# untitled.net
KiCad netlist of a schematic drawn in EAGLE
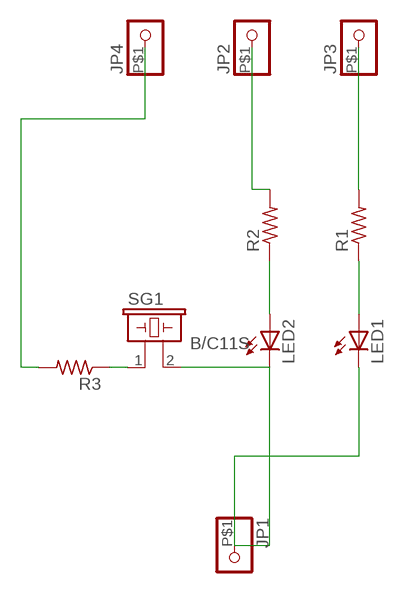
[diagram p0: schematic, sheet 1]

(export (version "E")
  (design (tool "Eeschema 10.0.6"))
  (components
    (comp (ref "JP1")
      (value "PINHD-1X1-BIGPOGO")
      (footprint "eagle-import:1X1-BIGPOGO")
      (libsource (lib "eagle-import") (part "PINHD-1X1-BIGPOGO"))
    )
    (comp (ref "JP2")
      (value "PINHD-1X1-BIGPOGO")
      (footprint "eagle-import:1X1-BIGPOGO")
      (libsource (lib "eagle-import") (part "PINHD-1X1-BIGPOGO"))
    )
    (comp (ref "JP3")
      (value "PINHD-1X1-BIGPOGO")
      (footprint "eagle-import:1X1-BIGPOGO")
      (libsource (lib "eagle-import") (part "PINHD-1X1-BIGPOGO"))
    )
    (comp (ref "JP4")
      (value "PINHD-1X1-BIGPOGO")
      (footprint "eagle-import:1X1-BIGPOGO")
      (libsource (lib "eagle-import") (part "PINHD-1X1-BIGPOGO"))
    )
    (comp (ref "LED1")
      (value "LEDB152")
      (footprint "eagle-import:Q62902-B152")
      (libsource (lib "eagle-import") (part "LEDB152"))
    )
    (comp (ref "LED2")
      (value "LEDB152")
      (footprint "eagle-import:Q62902-B152")
      (libsource (lib "eagle-import") (part "LEDB152"))
    )
    (comp (ref "R1")
      (value "FLIPFLOP-RES")
      (footprint "eagle-import:0805-THM")
      (libsource (lib "eagle-import") (part "FLIPFLOP-RES"))
    )
    (comp (ref "R2")
      (value "FLIPFLOP-RES")
      (footprint "eagle-import:0805-THM")
      (libsource (lib "eagle-import") (part "FLIPFLOP-RES"))
    )
    (comp (ref "R3")
      (value "FLIPFLOP-RES")
      (footprint "eagle-import:0805-THM")
      (libsource (lib "eagle-import") (part "FLIPFLOP-RES"))
    )
    (comp (ref "SG1")
      (value "B/C11S")
      (footprint "eagle-import:B_C11S")
      (libsource (lib "eagle-import") (part "B/C11S"))
    )
  )
  (nets
    (net (code "1") (name "Net-(JP1-1)") (class "Default")
      (node (ref "JP1") (pin "P$1") (pinfunction "1_P$1") (pintype "passive"))
      (node (ref "LED1") (pin "K") (pinfunction "C_K") (pintype "passive"))
      (node (ref "LED2") (pin "K") (pinfunction "C_K") (pintype "passive"))
      (node (ref "SG1") (pin "2") (pinfunction "2_2") (pintype "passive"))
    )
    (net (code "2") (name "Net-(JP2-1)") (class "Default")
      (node (ref "JP2") (pin "P$1") (pinfunction "1_P$1") (pintype "passive"))
      (node (ref "R2") (pin "2") (pinfunction "2_2") (pintype "passive"))
    )
    (net (code "3") (name "Net-(JP3-1)") (class "Default")
      (node (ref "JP3") (pin "P$1") (pinfunction "1_P$1") (pintype "passive"))
      (node (ref "R1") (pin "2") (pinfunction "2_2") (pintype "passive"))
    )
    (net (code "4") (name "Net-(JP4-1)") (class "Default")
      (node (ref "JP4") (pin "P$1") (pinfunction "1_P$1") (pintype "passive"))
      (node (ref "R3") (pin "2") (pinfunction "2_2") (pintype "passive"))
    )
    (net (code "5") (name "Net-(LED1-PadA)") (class "Default")
      (node (ref "LED1") (pin "A") (pinfunction "A_A") (pintype "passive"))
      (node (ref "R1") (pin "1") (pinfunction "1_1") (pintype "passive"))
    )
    (net (code "6") (name "Net-(LED2-PadA)") (class "Default")
      (node (ref "LED2") (pin "A") (pinfunction "A_A") (pintype "passive"))
      (node (ref "R2") (pin "1") (pinfunction "1_1") (pintype "passive"))
    )
    (net (code "7") (name "Net-(R3-Pad1)") (class "Default")
      (node (ref "R3") (pin "1") (pinfunction "1_1") (pintype "passive"))
      (node (ref "SG1") (pin "1") (pinfunction "1_1") (pintype "passive"))
    )
  )
)
